# 04-lnterface1.net
KiCad netlist of a schematic drawn in Altium Designer
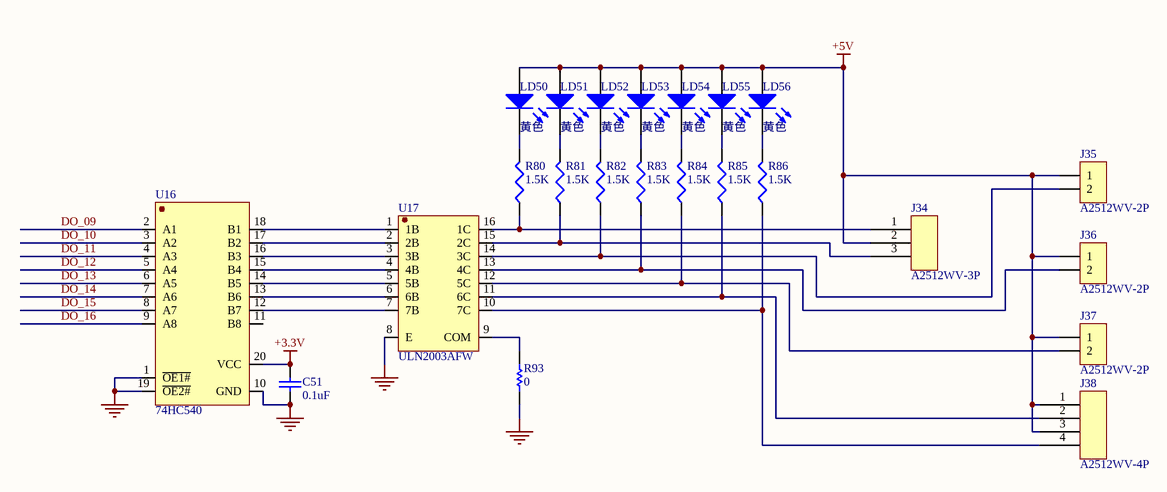
[diagram p0: 04-lnterface1.SchDoc]

(export (version "E")
  (design (tool "Eeschema 10.0.6"))
  (components
    (comp (ref "C51")
      (value "0.1uF")
      (footprint "C0805")
      (description "Capacitor")
      (fields (field (name "Comment") "Cap") (field (name "PUBLISHER") "Altium Limited"))
      (libsource (lib "Miscellaneous Devices") (part "Cap"))
    )
    (comp (ref "J34")
      (value "A2512WV-3P")
      (footprint "A2512WV-3P")
      (libsource (lib "SCHLIB") (part "A2512WV-3P"))
    )
    (comp (ref "J35")
      (value "A2512WV-2P")
      (footprint "A2512WV-2P")
      (libsource (lib "SCHLIB") (part "A2512WV-2P"))
    )
    (comp (ref "J36")
      (value "A2512WV-2P")
      (footprint "A2512WV-2P")
      (libsource (lib "SCHLIB") (part "A2512WV-2P"))
    )
    (comp (ref "J37")
      (value "A2512WV-2P")
      (footprint "A2512WV-2P")
      (libsource (lib "SCHLIB") (part "A2512WV-2P"))
    )
    (comp (ref "J38")
      (value "A2512WV-4P")
      (footprint "A2512WV-4P")
      (libsource (lib "SCHLIB") (part "A2512WV-4P"))
    )
    (comp (ref "LD50")
      (value "黄色")
      (footprint "LED0805")
      (description "Typical INFRARED GaAs LED")
      (fields (field (name "PUBLISHER") "Altium Limited"))
      (libsource (lib "Miscellaneous Devices") (part "LED0"))
    )
    (comp (ref "LD51")
      (value "黄色")
      (footprint "LED0805")
      (description "Typical INFRARED GaAs LED")
      (fields (field (name "PUBLISHER") "Altium Limited"))
      (libsource (lib "Miscellaneous Devices") (part "LED0"))
    )
    (comp (ref "LD52")
      (value "黄色")
      (footprint "LED0805")
      (description "Typical INFRARED GaAs LED")
      (fields (field (name "PUBLISHER") "Altium Limited"))
      (libsource (lib "Miscellaneous Devices") (part "LED0"))
    )
    (comp (ref "LD53")
      (value "黄色")
      (footprint "LED0805")
      (description "Typical INFRARED GaAs LED")
      (fields (field (name "PUBLISHER") "Altium Limited"))
      (libsource (lib "Miscellaneous Devices") (part "LED0"))
    )
    (comp (ref "LD54")
      (value "黄色")
      (footprint "LED0805")
      (description "Typical INFRARED GaAs LED")
      (fields (field (name "PUBLISHER") "Altium Limited"))
      (libsource (lib "Miscellaneous Devices") (part "LED0"))
    )
    (comp (ref "LD55")
      (value "黄色")
      (footprint "LED0805")
      (description "Typical INFRARED GaAs LED")
      (fields (field (name "PUBLISHER") "Altium Limited"))
      (libsource (lib "Miscellaneous Devices") (part "LED0"))
    )
    (comp (ref "LD56")
      (value "黄色")
      (footprint "LED0805")
      (description "Typical INFRARED GaAs LED")
      (fields (field (name "PUBLISHER") "Altium Limited"))
      (libsource (lib "Miscellaneous Devices") (part "LED0"))
    )
    (comp (ref "R80")
      (value "1.5K")
      (footprint "R0805")
      (description "Resistor")
      (fields (field (name "Comment") "Res3") (field (name "PUBLISHER") "Altium Limited"))
      (libsource (lib "Miscellaneous Devices") (part "Res3"))
    )
    (comp (ref "R81")
      (value "1.5K")
      (footprint "R0805")
      (description "Resistor")
      (fields (field (name "Comment") "Res3") (field (name "PUBLISHER") "Altium Limited"))
      (libsource (lib "Miscellaneous Devices") (part "Res3"))
    )
    (comp (ref "R82")
      (value "1.5K")
      (footprint "R0805")
      (description "Resistor")
      (fields (field (name "Comment") "Res3") (field (name "PUBLISHER") "Altium Limited"))
      (libsource (lib "Miscellaneous Devices") (part "Res3"))
    )
    (comp (ref "R83")
      (value "1.5K")
      (footprint "R0805")
      (description "Resistor")
      (fields (field (name "Comment") "Res3") (field (name "PUBLISHER") "Altium Limited"))
      (libsource (lib "Miscellaneous Devices") (part "Res3"))
    )
    (comp (ref "R84")
      (value "1.5K")
      (footprint "R0805")
      (description "Resistor")
      (fields (field (name "Comment") "Res3") (field (name "PUBLISHER") "Altium Limited"))
      (libsource (lib "Miscellaneous Devices") (part "Res3"))
    )
    (comp (ref "R85")
      (value "1.5K")
      (footprint "R0805")
      (description "Resistor")
      (fields (field (name "Comment") "Res3") (field (name "PUBLISHER") "Altium Limited"))
      (libsource (lib "Miscellaneous Devices") (part "Res3"))
    )
    (comp (ref "R86")
      (value "1.5K")
      (footprint "R0805")
      (description "Resistor")
      (fields (field (name "Comment") "Res3") (field (name "PUBLISHER") "Altium Limited"))
      (libsource (lib "Miscellaneous Devices") (part "Res3"))
    )
    (comp (ref "R93")
      (value "0")
      (footprint "R0805")
      (fields (field (name "PARAMETER 1") "0"))
      (libsource (lib "SCHLIB") (part "R 1206"))
    )
    (comp (ref "U16") (value "74HC540") (footprint "SOP-20") (libsource (lib "SCHLIB") (part "74HC540")))
    (comp (ref "U17")
      (value "ULN2003AFW")
      (footprint "SO-16P")
      (libsource (lib "SCHLIB") (part "ULN2003AFW"))
    )
  )
  (nets
    (net (code "1") (name "+3.3V") (class "Default")
      (node (ref "C51") (pin "2") (pinfunction "2_2") (pintype "passive"))
      (node (ref "U16") (pin "20") (pinfunction "VCC_20") (pintype "passive"))
    )
    (net (code "2") (name "+5V") (class "Default")
      (node (ref "J34") (pin "2") (pinfunction "2_2") (pintype "passive"))
      (node (ref "J35") (pin "1") (pinfunction "1_1") (pintype "passive"))
      (node (ref "J36") (pin "1") (pinfunction "1_1") (pintype "passive"))
      (node (ref "J37") (pin "1") (pinfunction "1_1") (pintype "passive"))
      (node (ref "J38") (pin "1") (pinfunction "1_1") (pintype "passive"))
      (node (ref "J38") (pin "3") (pinfunction "3_3") (pintype "passive"))
      (node (ref "LD50") (pin "1") (pinfunction "A_1") (pintype "passive"))
      (node (ref "LD51") (pin "1") (pinfunction "A_1") (pintype "passive"))
      (node (ref "LD52") (pin "1") (pinfunction "A_1") (pintype "passive"))
      (node (ref "LD53") (pin "1") (pinfunction "A_1") (pintype "passive"))
      (node (ref "LD54") (pin "1") (pinfunction "A_1") (pintype "passive"))
      (node (ref "LD55") (pin "1") (pinfunction "A_1") (pintype "passive"))
      (node (ref "LD56") (pin "1") (pinfunction "A_1") (pintype "passive"))
    )
    (net (code "3") (name "/DO_09") (class "Default")
      (node (ref "U16") (pin "2") (pinfunction "A1_2") (pintype "passive"))
    )
    (net (code "4") (name "/DO_10") (class "Default")
      (node (ref "U16") (pin "3") (pinfunction "A2_3") (pintype "passive"))
    )
    (net (code "5") (name "/DO_11") (class "Default")
      (node (ref "U16") (pin "4") (pinfunction "A3_4") (pintype "passive"))
    )
    (net (code "6") (name "/DO_12") (class "Default")
      (node (ref "U16") (pin "5") (pinfunction "A4_5") (pintype "passive"))
    )
    (net (code "7") (name "/DO_13") (class "Default")
      (node (ref "U16") (pin "6") (pinfunction "A5_6") (pintype "passive"))
    )
    (net (code "8") (name "/DO_14") (class "Default")
      (node (ref "U16") (pin "7") (pinfunction "A6_7") (pintype "passive"))
    )
    (net (code "9") (name "/DO_15") (class "Default")
      (node (ref "U16") (pin "8") (pinfunction "A7_8") (pintype "passive"))
    )
    (net (code "10") (name "/DO_16") (class "Default")
      (node (ref "U16") (pin "9") (pinfunction "A8_9") (pintype "passive"))
    )
    (net (code "11") (name "GND") (class "Default")
      (node (ref "C51") (pin "1") (pinfunction "1_1") (pintype "passive"))
      (node (ref "R93") (pin "1") (pinfunction "1_1") (pintype "passive"))
      (node (ref "U16") (pin "1") (pinfunction "~{OE1#}_1") (pintype "passive"))
      (node (ref "U16") (pin "10") (pinfunction "GND_10") (pintype "passive"))
      (node (ref "U16") (pin "19") (pinfunction "~{OE2#}_19") (pintype "passive"))
      (node (ref "U17") (pin "8") (pinfunction "E_8") (pintype "passive"))
    )
    (net (code "12") (name "Net-(LD50-K)") (class "Default")
      (node (ref "LD50") (pin "2") (pinfunction "K_2") (pintype "passive"))
      (node (ref "R80") (pin "2") (pinfunction "2_2") (pintype "passive"))
    )
    (net (code "13") (name "Net-(LD51-K)") (class "Default")
      (node (ref "LD51") (pin "2") (pinfunction "K_2") (pintype "passive"))
      (node (ref "R81") (pin "2") (pinfunction "2_2") (pintype "passive"))
    )
    (net (code "14") (name "Net-(LD52-K)") (class "Default")
      (node (ref "LD52") (pin "2") (pinfunction "K_2") (pintype "passive"))
      (node (ref "R82") (pin "2") (pinfunction "2_2") (pintype "passive"))
    )
    (net (code "15") (name "Net-(LD53-K)") (class "Default")
      (node (ref "LD53") (pin "2") (pinfunction "K_2") (pintype "passive"))
      (node (ref "R83") (pin "2") (pinfunction "2_2") (pintype "passive"))
    )
    (net (code "16") (name "Net-(LD54-K)") (class "Default")
      (node (ref "LD54") (pin "2") (pinfunction "K_2") (pintype "passive"))
      (node (ref "R84") (pin "2") (pinfunction "2_2") (pintype "passive"))
    )
    (net (code "17") (name "Net-(LD55-K)") (class "Default")
      (node (ref "LD55") (pin "2") (pinfunction "K_2") (pintype "passive"))
      (node (ref "R85") (pin "2") (pinfunction "2_2") (pintype "passive"))
    )
    (net (code "18") (name "Net-(LD56-K)") (class "Default")
      (node (ref "LD56") (pin "2") (pinfunction "K_2") (pintype "passive"))
      (node (ref "R86") (pin "2") (pinfunction "2_2") (pintype "passive"))
    )
    (net (code "19") (name "Net-(U16-B1)") (class "Default")
      (node (ref "U16") (pin "18") (pinfunction "B1_18") (pintype "passive"))
      (node (ref "U17") (pin "1") (pinfunction "1B_1") (pintype "passive"))
    )
    (net (code "20") (name "Net-(U16-B2)") (class "Default")
      (node (ref "U16") (pin "17") (pinfunction "B2_17") (pintype "passive"))
      (node (ref "U17") (pin "2") (pinfunction "2B_2") (pintype "passive"))
    )
    (net (code "21") (name "Net-(U16-B3)") (class "Default")
      (node (ref "U16") (pin "16") (pinfunction "B3_16") (pintype "passive"))
      (node (ref "U17") (pin "3") (pinfunction "3B_3") (pintype "passive"))
    )
    (net (code "22") (name "Net-(U16-B4)") (class "Default")
      (node (ref "U16") (pin "15") (pinfunction "B4_15") (pintype "passive"))
      (node (ref "U17") (pin "4") (pinfunction "4B_4") (pintype "passive"))
    )
    (net (code "23") (name "Net-(U16-B5)") (class "Default")
      (node (ref "U16") (pin "14") (pinfunction "B5_14") (pintype "passive"))
      (node (ref "U17") (pin "5") (pinfunction "5B_5") (pintype "passive"))
    )
    (net (code "24") (name "Net-(U16-B6)") (class "Default")
      (node (ref "U16") (pin "13") (pinfunction "B6_13") (pintype "passive"))
      (node (ref "U17") (pin "6") (pinfunction "6B_6") (pintype "passive"))
    )
    (net (code "25") (name "Net-(U16-B7)") (class "Default")
      (node (ref "U16") (pin "12") (pinfunction "B7_12") (pintype "passive"))
      (node (ref "U17") (pin "7") (pinfunction "7B_7") (pintype "passive"))
    )
    (net (code "26") (name "Net-(U17-1C)") (class "Default")
      (node (ref "J34") (pin "1") (pinfunction "1_1") (pintype "passive"))
      (node (ref "R80") (pin "1") (pinfunction "1_1") (pintype "passive"))
      (node (ref "U17") (pin "16") (pinfunction "1C_16") (pintype "passive"))
    )
    (net (code "27") (name "Net-(U17-2C)") (class "Default")
      (node (ref "J34") (pin "3") (pinfunction "3_3") (pintype "passive"))
      (node (ref "R81") (pin "1") (pinfunction "1_1") (pintype "passive"))
      (node (ref "U17") (pin "15") (pinfunction "2C_15") (pintype "passive"))
    )
    (net (code "28") (name "Net-(U17-3C)") (class "Default")
      (node (ref "J35") (pin "2") (pinfunction "2_2") (pintype "passive"))
      (node (ref "R82") (pin "1") (pinfunction "1_1") (pintype "passive"))
      (node (ref "U17") (pin "14") (pinfunction "3C_14") (pintype "passive"))
    )
    (net (code "29") (name "Net-(U17-4C)") (class "Default")
      (node (ref "J36") (pin "2") (pinfunction "2_2") (pintype "passive"))
      (node (ref "R83") (pin "1") (pinfunction "1_1") (pintype "passive"))
      (node (ref "U17") (pin "13") (pinfunction "4C_13") (pintype "passive"))
    )
    (net (code "30") (name "Net-(U17-5C)") (class "Default")
      (node (ref "J37") (pin "2") (pinfunction "2_2") (pintype "passive"))
      (node (ref "R84") (pin "1") (pinfunction "1_1") (pintype "passive"))
      (node (ref "U17") (pin "12") (pinfunction "5C_12") (pintype "passive"))
    )
    (net (code "31") (name "Net-(U17-6C)") (class "Default")
      (node (ref "J38") (pin "2") (pinfunction "2_2") (pintype "passive"))
      (node (ref "R85") (pin "1") (pinfunction "1_1") (pintype "passive"))
      (node (ref "U17") (pin "11") (pinfunction "6C_11") (pintype "passive"))
    )
    (net (code "32") (name "Net-(U17-7C)") (class "Default")
      (node (ref "J38") (pin "4") (pinfunction "4_4") (pintype "passive"))
      (node (ref "R86") (pin "1") (pinfunction "1_1") (pintype "passive"))
      (node (ref "U17") (pin "10") (pinfunction "7C_10") (pintype "passive"))
    )
    (net (code "33") (name "Net-(U17-COM)") (class "Default")
      (node (ref "R93") (pin "2") (pinfunction "2_2") (pintype "passive"))
      (node (ref "U17") (pin "9") (pinfunction "COM_9") (pintype "passive"))
    )
    (net (code "34") (name "unconnected-(U16-B8-Pad11)") (class "Default")
      (node (ref "U16") (pin "11") (pinfunction "B8_11") (pintype "passive"))
    )
  )
)
